# 06-SNESDRONE_Direct_IO_ARTY_Z7.net
KiCad netlist of a schematic drawn in Altium Designer
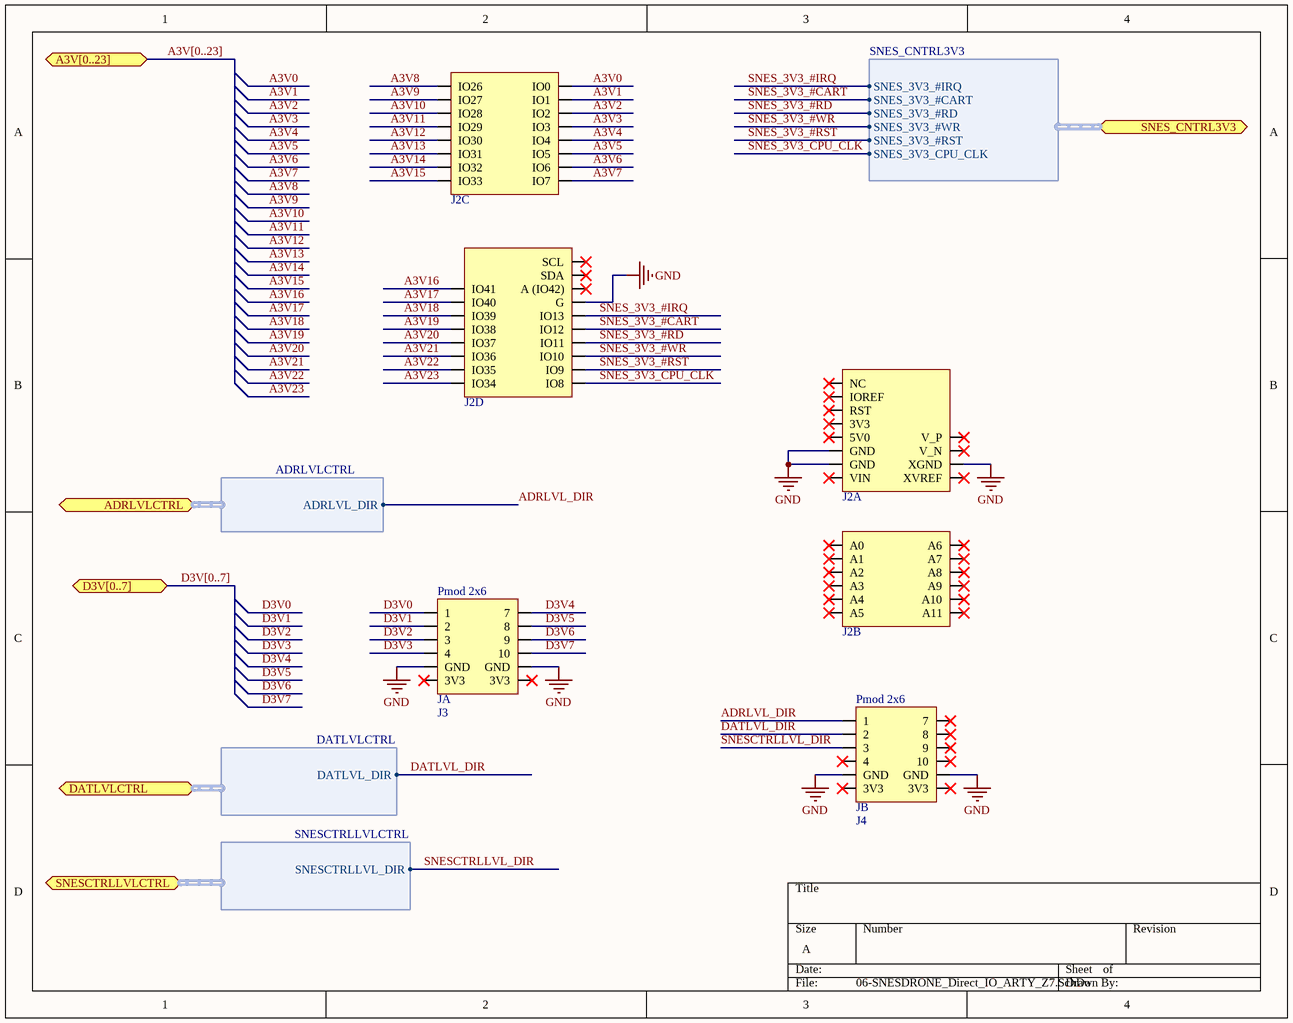
[diagram p0: 06-SNESDRONE_Direct_IO_ARTY_Z7.SchDoc]

(export (version "E")
  (design (tool "Eeschema 10.0.6"))
  (components
    (comp (ref "J2")
      (value "ARTY_Z7")
      (footprint "arty-z7")
      (description "Connections to Arty Z7 SoC Board")
      (libsource (lib "mycomponents") (part "ARTY_Z7"))
    )
    (comp (ref "J3")
      (value "ARTY_Z7_PMOD_A")
      (footprint "arty-z7-pmod")
      (description "Connections to Arty Z7 SoC Board")
      (libsource (lib "mycomponents") (part "ARTY_Z7_PMOD_A"))
    )
    (comp (ref "J4")
      (value "ARTY_Z7_PMOD_B")
      (footprint "arty-z7-pmod")
      (description "Connections to Arty Z7 SoC Board")
      (libsource (lib "mycomponents") (part "ARTY_Z7_PMOD_B"))
    )
  )
  (nets
    (net (code "5") (name "/A3V0") (class "Default")
      (node (ref "J2") (pin "32") (pinfunction "IO0_32") (pintype "passive"))
    )
    (net (code "6") (name "/A3V1") (class "Default")
      (node (ref "J2") (pin "33") (pinfunction "IO1_33") (pintype "passive"))
    )
    (net (code "7") (name "/A3V2") (class "Default")
      (node (ref "J2") (pin "34") (pinfunction "IO2_34") (pintype "passive"))
    )
    (net (code "8") (name "/A3V3") (class "Default")
      (node (ref "J2") (pin "35") (pinfunction "IO3_35") (pintype "passive"))
    )
    (net (code "9") (name "/A3V4") (class "Default")
      (node (ref "J2") (pin "36") (pinfunction "IO4_36") (pintype "passive"))
    )
    (net (code "10") (name "/A3V5") (class "Default")
      (node (ref "J2") (pin "37") (pinfunction "IO5_37") (pintype "passive"))
    )
    (net (code "11") (name "/A3V6") (class "Default")
      (node (ref "J2") (pin "38") (pinfunction "IO6_38") (pintype "passive"))
    )
    (net (code "12") (name "/A3V7") (class "Default")
      (node (ref "J2") (pin "39") (pinfunction "IO7_39") (pintype "passive"))
    )
    (net (code "13") (name "/A3V8") (class "Default")
      (node (ref "J2") (pin "31") (pinfunction "IO26_31") (pintype "passive"))
    )
    (net (code "14") (name "/A3V9") (class "Default")
      (node (ref "J2") (pin "30") (pinfunction "IO27_30") (pintype "passive"))
    )
    (net (code "15") (name "/A3V10") (class "Default")
      (node (ref "J2") (pin "29") (pinfunction "IO28_29") (pintype "passive"))
    )
    (net (code "16") (name "/A3V11") (class "Default")
      (node (ref "J2") (pin "28") (pinfunction "IO29_28") (pintype "passive"))
    )
    (net (code "17") (name "/A3V12") (class "Default")
      (node (ref "J2") (pin "27") (pinfunction "IO30_27") (pintype "passive"))
    )
    (net (code "18") (name "/A3V13") (class "Default")
      (node (ref "J2") (pin "26") (pinfunction "IO31_26") (pintype "passive"))
    )
    (net (code "19") (name "/A3V14") (class "Default")
      (node (ref "J2") (pin "25") (pinfunction "IO32_25") (pintype "passive"))
    )
    (net (code "20") (name "/A3V15") (class "Default")
      (node (ref "J2") (pin "24") (pinfunction "IO33_24") (pintype "passive"))
    )
    (net (code "21") (name "/A3V16") (class "Default")
      (node (ref "J2") (pin "40") (pinfunction "IO41_40") (pintype "passive"))
    )
    (net (code "22") (name "/A3V17") (class "Default")
      (node (ref "J2") (pin "41") (pinfunction "IO40_41") (pintype "passive"))
    )
    (net (code "23") (name "/A3V18") (class "Default")
      (node (ref "J2") (pin "42") (pinfunction "IO39_42") (pintype "passive"))
    )
    (net (code "24") (name "/A3V19") (class "Default")
      (node (ref "J2") (pin "43") (pinfunction "IO38_43") (pintype "passive"))
    )
    (net (code "25") (name "/A3V20") (class "Default")
      (node (ref "J2") (pin "44") (pinfunction "IO37_44") (pintype "passive"))
    )
    (net (code "26") (name "/A3V21") (class "Default")
      (node (ref "J2") (pin "45") (pinfunction "IO36_45") (pintype "passive"))
    )
    (net (code "27") (name "/A3V22") (class "Default")
      (node (ref "J2") (pin "46") (pinfunction "IO35_46") (pintype "passive"))
    )
    (net (code "28") (name "/A3V23") (class "Default")
      (node (ref "J2") (pin "47") (pinfunction "IO34_47") (pintype "passive"))
    )
    (net (code "30") (name "/ADRLVL_DIR") (class "Default")
      (node (ref "J4") (pin "0") (pinfunction "1_0") (pintype "passive"))
    )
    (net (code "31") (name "/D3V0") (class "Default")
      (node (ref "J3") (pin "0") (pinfunction "1_0") (pintype "passive"))
    )
    (net (code "32") (name "/D3V1") (class "Default")
      (node (ref "J3") (pin "1") (pinfunction "2_1") (pintype "passive"))
    )
    (net (code "33") (name "/D3V2") (class "Default")
      (node (ref "J3") (pin "2") (pinfunction "3_2") (pintype "passive"))
    )
    (net (code "34") (name "/D3V3") (class "Default")
      (node (ref "J3") (pin "3") (pinfunction "4_3") (pintype "passive"))
    )
    (net (code "35") (name "/D3V4") (class "Default")
      (node (ref "J3") (pin "11") (pinfunction "7_11") (pintype "passive"))
    )
    (net (code "36") (name "/D3V5") (class "Default")
      (node (ref "J3") (pin "10") (pinfunction "8_10") (pintype "passive"))
    )
    (net (code "37") (name "/D3V6") (class "Default")
      (node (ref "J3") (pin "9") (pinfunction "9_9") (pintype "passive"))
    )
    (net (code "38") (name "/D3V7") (class "Default")
      (node (ref "J3") (pin "8") (pinfunction "10_8") (pintype "passive"))
    )
    (net (code "40") (name "/DATLVL_DIR") (class "Default")
      (node (ref "J4") (pin "1") (pinfunction "2_1") (pintype "passive"))
    )
    (net (code "41") (name "/SNESCTRLLVL_DIR") (class "Default")
      (node (ref "J4") (pin "2") (pinfunction "3_2") (pintype "passive"))
    )
    (net (code "42") (name "/SNES_3V3_#CART") (class "Default")
      (node (ref "J2") (pin "52") (pinfunction "IO12_52") (pintype "passive"))
    )
    (net (code "43") (name "/SNES_3V3_#IRQ") (class "Default")
      (node (ref "J2") (pin "53") (pinfunction "IO13_53") (pintype "passive"))
    )
    (net (code "44") (name "/SNES_3V3_#RD") (class "Default")
      (node (ref "J2") (pin "51") (pinfunction "IO11_51") (pintype "passive"))
    )
    (net (code "45") (name "/SNES_3V3_#RST") (class "Default")
      (node (ref "J2") (pin "49") (pinfunction "IO9_49") (pintype "passive"))
    )
    (net (code "46") (name "/SNES_3V3_#WR") (class "Default")
      (node (ref "J2") (pin "50") (pinfunction "IO10_50") (pintype "passive"))
    )
    (net (code "47") (name "/SNES_3V3_CPU_CLK") (class "Default")
      (node (ref "J2") (pin "48") (pinfunction "IO8_48") (pintype "passive"))
    )
    (net (code "52") (name "GND") (class "Default")
      (node (ref "J2") (pin "5") (pinfunction "GND_5") (pintype "passive"))
      (node (ref "J2") (pin "54") (pinfunction "G_54") (pintype "passive"))
      (node (ref "J2") (pin "6") (pinfunction "GND_6") (pintype "passive"))
      (node (ref "J2") (pin "9") (pinfunction "XGND_9") (pintype "passive"))
      (node (ref "J3") (pin "4") (pinfunction "GND_4") (pintype "passive"))
      (node (ref "J3") (pin "7") (pinfunction "GND_7") (pintype "passive"))
      (node (ref "J4") (pin "4") (pinfunction "GND_4") (pintype "passive"))
      (node (ref "J4") (pin "7") (pinfunction "GND_7") (pintype "passive"))
    )
    (net (code "53") (name "unconnected-(J2A-3V3-Pad3)") (class "Default")
      (node (ref "J2") (pin "3") (pinfunction "3V3_3") (pintype "passive+no_connect"))
    )
    (net (code "54") (name "unconnected-(J2A-5V0-Pad4)") (class "Default")
      (node (ref "J2") (pin "4") (pinfunction "5V0_4") (pintype "passive+no_connect"))
    )
    (net (code "55") (name "unconnected-(J2A-IOREF-Pad1)") (class "Default")
      (node (ref "J2") (pin "1") (pinfunction "IOREF_1") (pintype "passive+no_connect"))
    )
    (net (code "56") (name "unconnected-(J2A-NC-Pad0)") (class "Default")
      (node (ref "J2") (pin "0") (pinfunction "NC_0") (pintype "passive+no_connect"))
    )
    (net (code "57") (name "unconnected-(J2A-RST-Pad2)") (class "Default")
      (node (ref "J2") (pin "2") (pinfunction "RST_2") (pintype "passive+no_connect"))
    )
    (net (code "58") (name "unconnected-(J2A-VIN-Pad7)") (class "Default")
      (node (ref "J2") (pin "7") (pinfunction "VIN_7") (pintype "passive+no_connect"))
    )
    (net (code "59") (name "unconnected-(J2A-V_N-Pad10)") (class "Default")
      (node (ref "J2") (pin "10") (pinfunction "V_N_10") (pintype "passive+no_connect"))
    )
    (net (code "60") (name "unconnected-(J2A-V_P-Pad11)") (class "Default")
      (node (ref "J2") (pin "11") (pinfunction "V_P_11") (pintype "passive+no_connect"))
    )
    (net (code "61") (name "unconnected-(J2A-XVREF-Pad8)") (class "Default")
      (node (ref "J2") (pin "8") (pinfunction "XVREF_8") (pintype "passive+no_connect"))
    )
    (net (code "62") (name "unconnected-(J2B-A0-Pad12)") (class "Default")
      (node (ref "J2") (pin "12") (pinfunction "A0_12") (pintype "passive+no_connect"))
    )
    (net (code "63") (name "unconnected-(J2B-A1-Pad13)") (class "Default")
      (node (ref "J2") (pin "13") (pinfunction "A1_13") (pintype "passive+no_connect"))
    )
    (net (code "64") (name "unconnected-(J2B-A2-Pad14)") (class "Default")
      (node (ref "J2") (pin "14") (pinfunction "A2_14") (pintype "passive+no_connect"))
    )
    (net (code "65") (name "unconnected-(J2B-A3-Pad15)") (class "Default")
      (node (ref "J2") (pin "15") (pinfunction "A3_15") (pintype "passive+no_connect"))
    )
    (net (code "66") (name "unconnected-(J2B-A4-Pad16)") (class "Default")
      (node (ref "J2") (pin "16") (pinfunction "A4_16") (pintype "passive+no_connect"))
    )
    (net (code "67") (name "unconnected-(J2B-A5-Pad17)") (class "Default")
      (node (ref "J2") (pin "17") (pinfunction "A5_17") (pintype "passive+no_connect"))
    )
    (net (code "68") (name "unconnected-(J2B-A6-Pad23)") (class "Default")
      (node (ref "J2") (pin "23") (pinfunction "A6_23") (pintype "passive+no_connect"))
    )
    (net (code "69") (name "unconnected-(J2B-A7-Pad22)") (class "Default")
      (node (ref "J2") (pin "22") (pinfunction "A7_22") (pintype "passive+no_connect"))
    )
    (net (code "70") (name "unconnected-(J2B-A8-Pad21)") (class "Default")
      (node (ref "J2") (pin "21") (pinfunction "A8_21") (pintype "passive+no_connect"))
    )
    (net (code "71") (name "unconnected-(J2B-A9-Pad20)") (class "Default")
      (node (ref "J2") (pin "20") (pinfunction "A9_20") (pintype "passive+no_connect"))
    )
    (net (code "72") (name "unconnected-(J2B-A10-Pad19)") (class "Default")
      (node (ref "J2") (pin "19") (pinfunction "A10_19") (pintype "passive+no_connect"))
    )
    (net (code "73") (name "unconnected-(J2B-A11-Pad18)") (class "Default")
      (node (ref "J2") (pin "18") (pinfunction "A11_18") (pintype "passive+no_connect"))
    )
    (net (code "74") (name "unconnected-(J2D-A_(IO42)-Pad55)") (class "Default")
      (node (ref "J2") (pin "55") (pinfunction "A_(IO42)_55") (pintype "passive+no_connect"))
    )
    (net (code "75") (name "unconnected-(J2D-SCL-Pad57)") (class "Default")
      (node (ref "J2") (pin "57") (pinfunction "SCL_57") (pintype "passive+no_connect"))
    )
    (net (code "76") (name "unconnected-(J2D-SDA-Pad56)") (class "Default")
      (node (ref "J2") (pin "56") (pinfunction "SDA_56") (pintype "passive+no_connect"))
    )
    (net (code "77") (name "unconnected-(J3-3V3-Pad5)") (class "Default")
      (node (ref "J3") (pin "5") (pinfunction "3V3_5") (pintype "passive+no_connect"))
    )
    (net (code "78") (name "unconnected-(J3-3V3-Pad6)") (class "Default")
      (node (ref "J3") (pin "6") (pinfunction "3V3_6") (pintype "passive+no_connect"))
    )
    (net (code "79") (name "unconnected-(J4-3V3-Pad5)") (class "Default")
      (node (ref "J4") (pin "5") (pinfunction "3V3_5") (pintype "passive+no_connect"))
    )
    (net (code "80") (name "unconnected-(J4-3V3-Pad6)") (class "Default")
      (node (ref "J4") (pin "6") (pinfunction "3V3_6") (pintype "passive+no_connect"))
    )
    (net (code "81") (name "unconnected-(J4-4-Pad3)") (class "Default")
      (node (ref "J4") (pin "3") (pinfunction "4_3") (pintype "passive+no_connect"))
    )
    (net (code "82") (name "unconnected-(J4-7-Pad11)") (class "Default")
      (node (ref "J4") (pin "11") (pinfunction "7_11") (pintype "passive+no_connect"))
    )
    (net (code "83") (name "unconnected-(J4-8-Pad10)") (class "Default")
      (node (ref "J4") (pin "10") (pinfunction "8_10") (pintype "passive+no_connect"))
    )
    (net (code "84") (name "unconnected-(J4-10-Pad8)") (class "Default")
      (node (ref "J4") (pin "8") (pinfunction "10_8") (pintype "passive+no_connect"))
    )
    (net (code "85") (name "unconnected-(J4-Pad9)") (class "Default")
      (node (ref "J4") (pin "9") (pinfunction "9_9") (pintype "passive+no_connect"))
    )
  )
)
